# Cell_121_sheet_4.net
KiCad netlist of a schematic drawn in Altium Designer
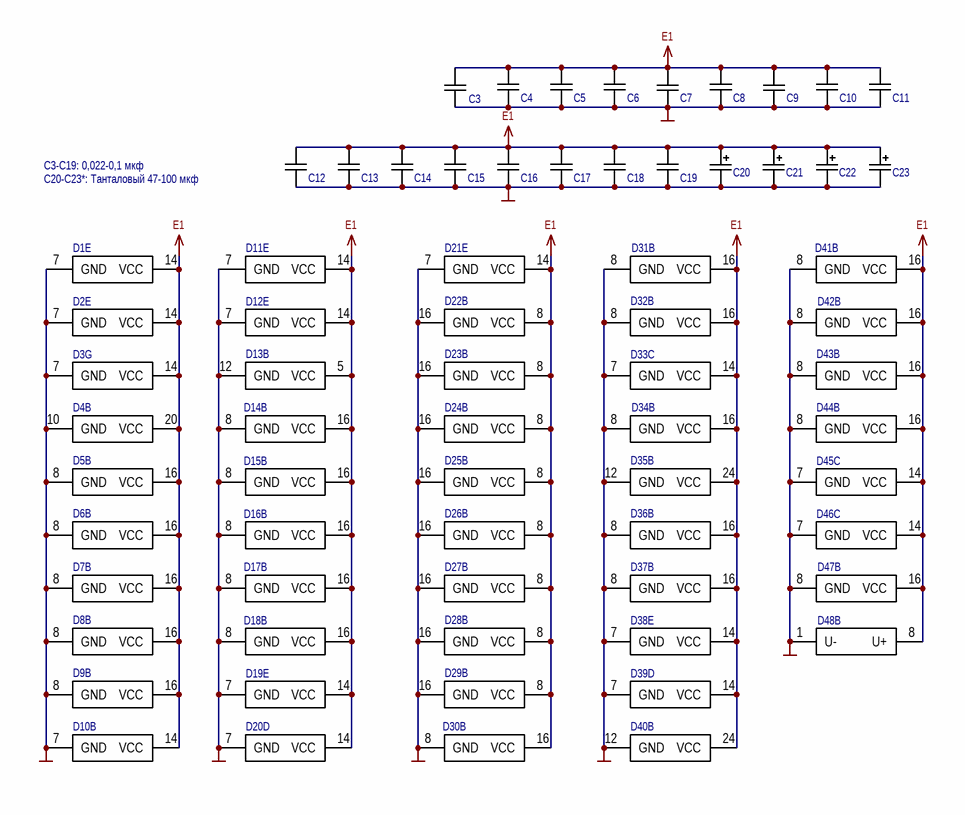
[diagram p0: Cell_121_sheet_4.SchDoc]

(export (version "E")
  (design (tool "Eeschema 10.0.6"))
  (components
    (comp (ref "C3")
      (value "0,1 мкф")
      (footprint "C5")
      (description "К10-17")
      (libsource (lib "Agat") (part "К10-17"))
    )
    (comp (ref "C4")
      (value "0,1 мкф")
      (footprint "C5")
      (description "К10-17")
      (libsource (lib "Agat") (part "К10-17"))
    )
    (comp (ref "C5")
      (value "0,1 мкф")
      (footprint "C5")
      (description "К10-17")
      (libsource (lib "Agat") (part "К10-17"))
    )
    (comp (ref "C6")
      (value "0,1 мкф")
      (footprint "C5")
      (description "К10-17")
      (libsource (lib "Agat") (part "К10-17"))
    )
    (comp (ref "C7")
      (value "0,1 мкф")
      (footprint "C5")
      (description "К10-17")
      (libsource (lib "Agat") (part "К10-17"))
    )
    (comp (ref "C8")
      (value "0,1 мкф")
      (footprint "C5")
      (description "К10-17")
      (libsource (lib "Agat") (part "К10-17"))
    )
    (comp (ref "C9")
      (value "0,1 мкф")
      (footprint "C5")
      (description "К10-17")
      (libsource (lib "Agat") (part "К10-17"))
    )
    (comp (ref "C10")
      (value "0,1 мкф")
      (footprint "C5")
      (description "К10-17")
      (libsource (lib "Agat") (part "К10-17"))
    )
    (comp (ref "C11")
      (value "0,1 мкф")
      (footprint "C5")
      (description "К10-17")
      (libsource (lib "Agat") (part "К10-17"))
    )
    (comp (ref "C12")
      (value "0,1 мкф")
      (footprint "C5")
      (description "К10-17")
      (libsource (lib "Agat") (part "К10-17"))
    )
    (comp (ref "C13")
      (value "0,1 мкф")
      (footprint "C5")
      (description "К10-17")
      (libsource (lib "Agat") (part "К10-17"))
    )
    (comp (ref "C14")
      (value "0,1 мкф")
      (footprint "C5")
      (description "К10-17")
      (libsource (lib "Agat") (part "К10-17"))
    )
    (comp (ref "C15")
      (value "0,1 мкф")
      (footprint "C5")
      (description "К10-17")
      (libsource (lib "Agat") (part "К10-17"))
    )
    (comp (ref "C16")
      (value "0,1 мкф")
      (footprint "C5")
      (description "К10-17")
      (libsource (lib "Agat") (part "К10-17"))
    )
    (comp (ref "C17")
      (value "0,1 мкф")
      (footprint "C5")
      (description "К10-17")
      (libsource (lib "Agat") (part "К10-17"))
    )
    (comp (ref "C18")
      (value "0,1 мкф")
      (footprint "C5")
      (description "К10-17")
      (libsource (lib "Agat") (part "К10-17"))
    )
    (comp (ref "C19")
      (value "0,1 мкф")
      (footprint "C5")
      (description "К10-17")
      (libsource (lib "Agat") (part "К10-17"))
    )
    (comp (ref "C20")
      (value "47 мкф")
      (footprint "SMD D")
      (description "К53-14")
      (libsource (lib "Agat") (part "К53-1"))
    )
    (comp (ref "C21")
      (value "47 мкф")
      (footprint "SMD D")
      (description "К53-14")
      (libsource (lib "Agat") (part "К53-1"))
    )
    (comp (ref "C22")
      (value "47 мкф")
      (footprint "SMD D")
      (description "К53-14")
      (libsource (lib "Agat") (part "К53-1"))
    )
    (comp (ref "C23")
      (value "47 мкф")
      (footprint "SMD D")
      (description "К53-14")
      (libsource (lib "Agat") (part "К53-1"))
    )
    (comp (ref "D1") (value "К555ЛИ1") (footprint "201.14") (libsource (lib "Agat") (part "К555ЛИ1")))
    (comp (ref "D2")
      (value "К555ЛЕ1")
      (footprint "201.14")
      (fields (field (name "MANUFACTURERPARTNUMBER") "К555ЛА3"))
      (libsource (lib "Agat") (part "К555ЛЕ1"))
    )
    (comp (ref "D3")
      (value "К555ЛН1")
      (footprint "201.14")
      (fields (field (name "MANUFACTURERPARTNUMBER") "К155ЛН1"))
      (libsource (lib "Agat") (part "К555ЛН1"))
    )
    (comp (ref "D4") (value "К555ИР22") (footprint "201.20") (libsource (lib "Agat") (part "К555ИР22")))
    (comp (ref "D5")
      (value "К555ИЕ10")
      (footprint "201.16")
      (fields (field (name "MANUFACTURERPARTNUMBER") "КР531ИЕ17"))
      (libsource (lib "Agat") (part "К555ИЕ10"))
    )
    (comp (ref "D6")
      (value "К555ИЕ10")
      (footprint "201.16")
      (fields (field (name "MANUFACTURERPARTNUMBER") "КР531ИЕ17"))
      (libsource (lib "Agat") (part "К555ИЕ10"))
    )
    (comp (ref "D7")
      (value "К555ИЕ10")
      (footprint "201.16")
      (fields (field (name "MANUFACTURERPARTNUMBER") "КР531ИЕ17"))
      (libsource (lib "Agat") (part "К555ИЕ10"))
    )
    (comp (ref "D8")
      (value "К555ИЕ10")
      (footprint "201.16")
      (fields (field (name "MANUFACTURERPARTNUMBER") "КР531ИЕ17"))
      (libsource (lib "Agat") (part "К555ИЕ10"))
    )
    (comp (ref "D9")
      (value "К555ИР11А")
      (footprint "201.16")
      (fields (field (name "MANUFACTURERPARTNUMBER") "КР531ИЕ17"))
      (libsource (lib "Agat") (part "К555ИР11А"))
    )
    (comp (ref "D10")
      (value "К555ИР16")
      (footprint "201.14")
      (fields (field (name "MANUFACTURERPARTNUMBER") "КР531ИЕ17"))
      (libsource (lib "Agat") (part "К555ИР16"))
    )
    (comp (ref "D11") (value "К555ЛА3") (footprint "201.14") (libsource (lib "Agat") (part "К555ЛА3")))
    (comp (ref "D12")
      (value "К555ЛП5")
      (footprint "201.14")
      (fields (field (name "MANUFACTURERPARTNUMBER") "К155ЛП5"))
      (libsource (lib "Agat") (part "К555ЛП5"))
    )
    (comp (ref "D13")
      (value "К155ИМ3")
      (footprint "201.16")
      (fields (field (name "MANUFACTURERPARTNUMBER") "SN74ALS138"))
      (libsource (lib "Agat") (part "К155ИМ3"))
    )
    (comp (ref "D14") (value "К555КП11") (footprint "201.16") (libsource (lib "Agat") (part "К555КП11")))
    (comp (ref "D15")
      (value "К555КП12")
      (footprint "201.16")
      (fields (field (name "MANUFACTURERPARTNUMBER") "К155КП2"))
      (libsource (lib "Agat") (part "К555КП12"))
    )
    (comp (ref "D16")
      (value "К555КП12")
      (footprint "201.16")
      (fields (field (name "MANUFACTURERPARTNUMBER") "К155КП2"))
      (libsource (lib "Agat") (part "К555КП12"))
    )
    (comp (ref "D17")
      (value "К555КП12")
      (footprint "201.16")
      (fields (field (name "MANUFACTURERPARTNUMBER") "К155КП2"))
      (libsource (lib "Agat") (part "К555КП12"))
    )
    (comp (ref "D18")
      (value "К555КП12")
      (footprint "201.16")
      (fields (field (name "MANUFACTURERPARTNUMBER") "К155КП2"))
      (libsource (lib "Agat") (part "К555КП12"))
    )
    (comp (ref "D19")
      (value "К555ЛЕ1")
      (footprint "201.14")
      (fields (field (name "MANUFACTURERPARTNUMBER") "К555ЛА3"))
      (libsource (lib "Agat") (part "К555ЛЕ1"))
    )
    (comp (ref "D20")
      (value "К555ЛИ3")
      (footprint "201.14")
      (fields (field (name "MANUFACTURERPARTNUMBER") "К555ЛА3"))
      (libsource (lib "Agat") (part "К555ЛИ3"))
    )
    (comp (ref "D21")
      (value "К555ЛЕ1")
      (footprint "201.14")
      (fields (field (name "MANUFACTURERPARTNUMBER") "К555ЛА3"))
      (libsource (lib "Agat") (part "К555ЛЕ1"))
    )
    (comp (ref "D22") (value "К565РУ5") (footprint "201.16") (libsource (lib "Agat") (part "К565РУ5")))
    (comp (ref "D23") (value "К565РУ5") (footprint "201.16") (libsource (lib "Agat") (part "К565РУ5")))
    (comp (ref "D24") (value "К565РУ5") (footprint "201.16") (libsource (lib "Agat") (part "К565РУ5")))
    (comp (ref "D25") (value "К565РУ5") (footprint "201.16") (libsource (lib "Agat") (part "К565РУ5")))
    (comp (ref "D26") (value "К565РУ5") (footprint "201.16") (libsource (lib "Agat") (part "К565РУ5")))
    (comp (ref "D27") (value "К565РУ5") (footprint "201.16") (libsource (lib "Agat") (part "К565РУ5")))
    (comp (ref "D28") (value "К565РУ5") (footprint "201.16") (libsource (lib "Agat") (part "К565РУ5")))
    (comp (ref "D29") (value "К565РУ5") (footprint "201.16") (libsource (lib "Agat") (part "К565РУ5")))
    (comp (ref "D30")
      (value "К555ТМ9")
      (footprint "201.16")
      (fields (field (name "MANUFACTURERPARTNUMBER") "SN74ALS174"))
      (libsource (lib "Agat") (part "К555ТМ9"))
    )
    (comp (ref "D31")
      (value "К555ТМ9")
      (footprint "201.16")
      (fields (field (name "MANUFACTURERPARTNUMBER") "SN74ALS174"))
      (libsource (lib "Agat") (part "К555ТМ9"))
    )
    (comp (ref "D32")
      (value "К555ИР11А")
      (footprint "201.16")
      (fields (field (name "MANUFACTURERPARTNUMBER") "КР531ИЕ17"))
      (libsource (lib "Agat") (part "К555ИР11А"))
    )
    (comp (ref "D33") (value "К555ТМ2") (footprint "201.14") (libsource (lib "Agat") (part "К555ТМ2")))
    (comp (ref "D34") (value "К555ИД4") (footprint "201.16") (libsource (lib "Agat") (part "К555ИД4")))
    (comp (ref "D35")
      (value "К573РФ2")
      (footprint "2120.24 socket")
      (libsource (lib "Agat") (part "К573РФ2"))
    )
    (comp (ref "D36")
      (value "К555ИР11А")
      (footprint "201.16")
      (fields (field (name "MANUFACTURERPARTNUMBER") "КР531ИЕ17"))
      (libsource (lib "Agat") (part "К555ИР11А"))
    )
    (comp (ref "D37")
      (value "К555ИР11А")
      (footprint "201.16")
      (fields (field (name "MANUFACTURERPARTNUMBER") "КР531ИЕ17"))
      (libsource (lib "Agat") (part "К555ИР11А"))
    )
    (comp (ref "D38") (value "К555ЛИ1") (footprint "201.14") (libsource (lib "Agat") (part "К555ЛИ1")))
    (comp (ref "D39")
      (value "К555ЛИ3")
      (footprint "201.14")
      (fields (field (name "MANUFACTURERPARTNUMBER") "К555ЛА3"))
      (libsource (lib "Agat") (part "К555ЛИ3"))
    )
    (comp (ref "D40") (value "К155ИР13") (footprint "2120.24") (libsource (lib "Agat") (part "К155ИР13")))
    (comp (ref "D41")
      (value "К555КП12")
      (footprint "201.16")
      (fields (field (name "MANUFACTURERPARTNUMBER") "К155КП2"))
      (libsource (lib "Agat") (part "К555КП12"))
    )
    (comp (ref "D42")
      (value "К555КП12")
      (footprint "201.16")
      (fields (field (name "MANUFACTURERPARTNUMBER") "К155КП2"))
      (libsource (lib "Agat") (part "К555КП12"))
    )
    (comp (ref "D43")
      (value "К555ИД7")
      (footprint "201.16")
      (fields (field (name "MANUFACTURERPARTNUMBER") "SN74ALS138"))
      (libsource (lib "Agat") (part "К555ИД7"))
    )
    (comp (ref "D44")
      (value "К555ИР11А")
      (footprint "201.16")
      (fields (field (name "MANUFACTURERPARTNUMBER") "КР531ИЕ17"))
      (libsource (lib "Agat") (part "К555ИР11А"))
    )
    (comp (ref "D45") (value "К555ТМ2") (footprint "201.14") (libsource (lib "Agat") (part "К555ТМ2")))
    (comp (ref "D46") (value "К555ТМ2") (footprint "201.14") (libsource (lib "Agat") (part "К555ТМ2")))
    (comp (ref "D47") (value "К555КП11") (footprint "201.16") (libsource (lib "Agat") (part "К555КП11")))
    (comp (ref "D48")
      (value "КР1006ВИ1")
      (footprint "2101.8")
      (fields (field (name "MANUFACTURERPARTNUMBER") "К555ИД4"))
      (libsource (lib "Agat") (part "КР1006ВИ1"))
    )
  )
  (nets
    (net (code "1") (name "E1") (class "Default")
      (node (ref "C10") (pin "2") (pintype "passive"))
      (node (ref "C11") (pin "2") (pintype "passive"))
      (node (ref "C12") (pin "2") (pintype "passive"))
      (node (ref "C13") (pin "2") (pintype "passive"))
      (node (ref "C14") (pin "2") (pintype "passive"))
      (node (ref "C15") (pin "2") (pintype "passive"))
      (node (ref "C16") (pin "2") (pintype "passive"))
      (node (ref "C17") (pin "2") (pintype "passive"))
      (node (ref "C18") (pin "2") (pintype "passive"))
      (node (ref "C19") (pin "2") (pintype "passive"))
      (node (ref "C20") (pin "1") (pintype "passive"))
      (node (ref "C21") (pin "1") (pintype "passive"))
      (node (ref "C22") (pin "1") (pintype "passive"))
      (node (ref "C23") (pin "1") (pintype "passive"))
      (node (ref "C3") (pin "1") (pintype "passive"))
      (node (ref "C4") (pin "2") (pintype "passive"))
      (node (ref "C5") (pin "2") (pintype "passive"))
      (node (ref "C6") (pin "2") (pintype "passive"))
      (node (ref "C7") (pin "1") (pintype "passive"))
      (node (ref "C8") (pin "2") (pintype "passive"))
      (node (ref "C9") (pin "1") (pintype "passive"))
      (node (ref "D1") (pin "14") (pinfunction "VCC_14") (pintype "passive"))
      (node (ref "D10") (pin "14") (pinfunction "VCC_14") (pintype "passive"))
      (node (ref "D11") (pin "14") (pinfunction "VCC_14") (pintype "passive"))
      (node (ref "D12") (pin "14") (pinfunction "VCC_14") (pintype "passive"))
      (node (ref "D13") (pin "5") (pinfunction "VCC_5") (pintype "passive"))
      (node (ref "D14") (pin "16") (pinfunction "VCC_16") (pintype "passive"))
      (node (ref "D15") (pin "16") (pinfunction "VCC_16") (pintype "passive"))
      (node (ref "D16") (pin "16") (pinfunction "VCC_16") (pintype "passive"))
      (node (ref "D17") (pin "16") (pinfunction "VCC_16") (pintype "passive"))
      (node (ref "D18") (pin "16") (pinfunction "VCC_16") (pintype "passive"))
      (node (ref "D19") (pin "14") (pinfunction "VCC_14") (pintype "passive"))
      (node (ref "D2") (pin "14") (pinfunction "VCC_14") (pintype "passive"))
      (node (ref "D20") (pin "14") (pinfunction "VCC_14") (pintype "passive"))
      (node (ref "D21") (pin "14") (pinfunction "VCC_14") (pintype "passive"))
      (node (ref "D22") (pin "8") (pinfunction "VCC_8") (pintype "passive"))
      (node (ref "D23") (pin "8") (pinfunction "VCC_8") (pintype "passive"))
      (node (ref "D24") (pin "8") (pinfunction "VCC_8") (pintype "passive"))
      (node (ref "D25") (pin "8") (pinfunction "VCC_8") (pintype "passive"))
      (node (ref "D26") (pin "8") (pinfunction "VCC_8") (pintype "passive"))
      (node (ref "D27") (pin "8") (pinfunction "VCC_8") (pintype "passive"))
      (node (ref "D28") (pin "8") (pinfunction "VCC_8") (pintype "passive"))
      (node (ref "D29") (pin "8") (pinfunction "VCC_8") (pintype "passive"))
      (node (ref "D3") (pin "14") (pinfunction "VCC_14") (pintype "passive"))
      (node (ref "D30") (pin "16") (pinfunction "VCC_16") (pintype "passive"))
      (node (ref "D31") (pin "16") (pinfunction "VCC_16") (pintype "passive"))
      (node (ref "D32") (pin "16") (pinfunction "VCC_16") (pintype "passive"))
      (node (ref "D33") (pin "14") (pinfunction "VCC_14") (pintype "passive"))
      (node (ref "D34") (pin "16") (pinfunction "VCC_16") (pintype "passive"))
      (node (ref "D35") (pin "24") (pinfunction "VCC_24") (pintype "passive"))
      (node (ref "D36") (pin "16") (pinfunction "VCC_16") (pintype "passive"))
      (node (ref "D37") (pin "16") (pinfunction "VCC_16") (pintype "passive"))
      (node (ref "D38") (pin "14") (pinfunction "VCC_14") (pintype "passive"))
      (node (ref "D39") (pin "14") (pinfunction "VCC_14") (pintype "passive"))
      (node (ref "D4") (pin "20") (pinfunction "VCC_20") (pintype "passive"))
      (node (ref "D40") (pin "24") (pinfunction "VCC_24") (pintype "passive"))
      (node (ref "D41") (pin "16") (pinfunction "VCC_16") (pintype "passive"))
      (node (ref "D42") (pin "16") (pinfunction "VCC_16") (pintype "passive"))
      (node (ref "D43") (pin "16") (pinfunction "VCC_16") (pintype "passive"))
      (node (ref "D44") (pin "16") (pinfunction "VCC_16") (pintype "passive"))
      (node (ref "D45") (pin "14") (pinfunction "VCC_14") (pintype "passive"))
      (node (ref "D46") (pin "14") (pinfunction "VCC_14") (pintype "passive"))
      (node (ref "D47") (pin "16") (pinfunction "VCC_16") (pintype "passive"))
      (node (ref "D48") (pin "8") (pinfunction "U+_8") (pintype "passive"))
      (node (ref "D5") (pin "16") (pinfunction "VCC_16") (pintype "passive"))
      (node (ref "D6") (pin "16") (pinfunction "VCC_16") (pintype "passive"))
      (node (ref "D7") (pin "16") (pinfunction "VCC_16") (pintype "passive"))
      (node (ref "D8") (pin "16") (pinfunction "VCC_16") (pintype "passive"))
      (node (ref "D9") (pin "16") (pinfunction "VCC_16") (pintype "passive"))
    )
    (net (code "2") (name "GND") (class "Default")
      (node (ref "C10") (pin "1") (pintype "passive"))
      (node (ref "C11") (pin "1") (pintype "passive"))
      (node (ref "C12") (pin "1") (pintype "passive"))
      (node (ref "C13") (pin "1") (pintype "passive"))
      (node (ref "C14") (pin "1") (pintype "passive"))
      (node (ref "C15") (pin "1") (pintype "passive"))
      (node (ref "C16") (pin "1") (pintype "passive"))
      (node (ref "C17") (pin "1") (pintype "passive"))
      (node (ref "C18") (pin "1") (pintype "passive"))
      (node (ref "C19") (pin "1") (pintype "passive"))
      (node (ref "C20") (pin "2") (pintype "passive"))
      (node (ref "C21") (pin "2") (pintype "passive"))
      (node (ref "C22") (pin "2") (pintype "passive"))
      (node (ref "C23") (pin "2") (pintype "passive"))
      (node (ref "C3") (pin "2") (pintype "passive"))
      (node (ref "C4") (pin "1") (pintype "passive"))
      (node (ref "C5") (pin "1") (pintype "passive"))
      (node (ref "C6") (pin "1") (pintype "passive"))
      (node (ref "C7") (pin "2") (pintype "passive"))
      (node (ref "C8") (pin "1") (pintype "passive"))
      (node (ref "C9") (pin "2") (pintype "passive"))
      (node (ref "D1") (pin "7") (pinfunction "GND_7") (pintype "passive"))
      (node (ref "D10") (pin "7") (pinfunction "GND_7") (pintype "passive"))
      (node (ref "D11") (pin "7") (pinfunction "GND_7") (pintype "passive"))
      (node (ref "D12") (pin "7") (pinfunction "GND_7") (pintype "passive"))
      (node (ref "D13") (pin "12") (pinfunction "GND_12") (pintype "passive"))
      (node (ref "D14") (pin "8") (pinfunction "GND_8") (pintype "passive"))
      (node (ref "D15") (pin "8") (pinfunction "GND_8") (pintype "passive"))
      (node (ref "D16") (pin "8") (pinfunction "GND_8") (pintype "passive"))
      (node (ref "D17") (pin "8") (pinfunction "GND_8") (pintype "passive"))
      (node (ref "D18") (pin "8") (pinfunction "GND_8") (pintype "passive"))
      (node (ref "D19") (pin "7") (pinfunction "GND_7") (pintype "passive"))
      (node (ref "D2") (pin "7") (pinfunction "GND_7") (pintype "passive"))
      (node (ref "D20") (pin "7") (pinfunction "GND_7") (pintype "passive"))
      (node (ref "D21") (pin "7") (pinfunction "GND_7") (pintype "passive"))
      (node (ref "D22") (pin "16") (pinfunction "GND_16") (pintype "passive"))
      (node (ref "D23") (pin "16") (pinfunction "GND_16") (pintype "passive"))
      (node (ref "D24") (pin "16") (pinfunction "GND_16") (pintype "passive"))
      (node (ref "D25") (pin "16") (pinfunction "GND_16") (pintype "passive"))
      (node (ref "D26") (pin "16") (pinfunction "GND_16") (pintype "passive"))
      (node (ref "D27") (pin "16") (pinfunction "GND_16") (pintype "passive"))
      (node (ref "D28") (pin "16") (pinfunction "GND_16") (pintype "passive"))
      (node (ref "D29") (pin "16") (pinfunction "GND_16") (pintype "passive"))
      (node (ref "D3") (pin "7") (pinfunction "GND_7") (pintype "passive"))
      (node (ref "D30") (pin "8") (pinfunction "GND_8") (pintype "passive"))
      (node (ref "D31") (pin "8") (pinfunction "GND_8") (pintype "passive"))
      (node (ref "D32") (pin "8") (pinfunction "GND_8") (pintype "passive"))
      (node (ref "D33") (pin "7") (pinfunction "GND_7") (pintype "passive"))
      (node (ref "D34") (pin "8") (pinfunction "GND_8") (pintype "passive"))
      (node (ref "D35") (pin "12") (pinfunction "GND_12") (pintype "passive"))
      (node (ref "D36") (pin "8") (pinfunction "GND_8") (pintype "passive"))
      (node (ref "D37") (pin "8") (pinfunction "GND_8") (pintype "passive"))
      (node (ref "D38") (pin "7") (pinfunction "GND_7") (pintype "passive"))
      (node (ref "D39") (pin "7") (pinfunction "GND_7") (pintype "passive"))
      (node (ref "D4") (pin "10") (pinfunction "GND_10") (pintype "passive"))
      (node (ref "D40") (pin "12") (pinfunction "GND_12") (pintype "passive"))
      (node (ref "D41") (pin "8") (pinfunction "GND_8") (pintype "passive"))
      (node (ref "D42") (pin "8") (pinfunction "GND_8") (pintype "passive"))
      (node (ref "D43") (pin "8") (pinfunction "GND_8") (pintype "passive"))
      (node (ref "D44") (pin "8") (pinfunction "GND_8") (pintype "passive"))
      (node (ref "D45") (pin "7") (pinfunction "GND_7") (pintype "passive"))
      (node (ref "D46") (pin "7") (pinfunction "GND_7") (pintype "passive"))
      (node (ref "D47") (pin "8") (pinfunction "GND_8") (pintype "passive"))
      (node (ref "D48") (pin "1") (pinfunction "U-_1") (pintype "passive"))
      (node (ref "D5") (pin "8") (pinfunction "GND_8") (pintype "passive"))
      (node (ref "D6") (pin "8") (pinfunction "GND_8") (pintype "passive"))
      (node (ref "D7") (pin "8") (pinfunction "GND_8") (pintype "passive"))
      (node (ref "D8") (pin "8") (pinfunction "GND_8") (pintype "passive"))
      (node (ref "D9") (pin "8") (pinfunction "GND_8") (pintype "passive"))
    )
  )
)
